# 16-MT7688AN_Power-F.net
KiCad netlist of a schematic drawn in Altium Designer
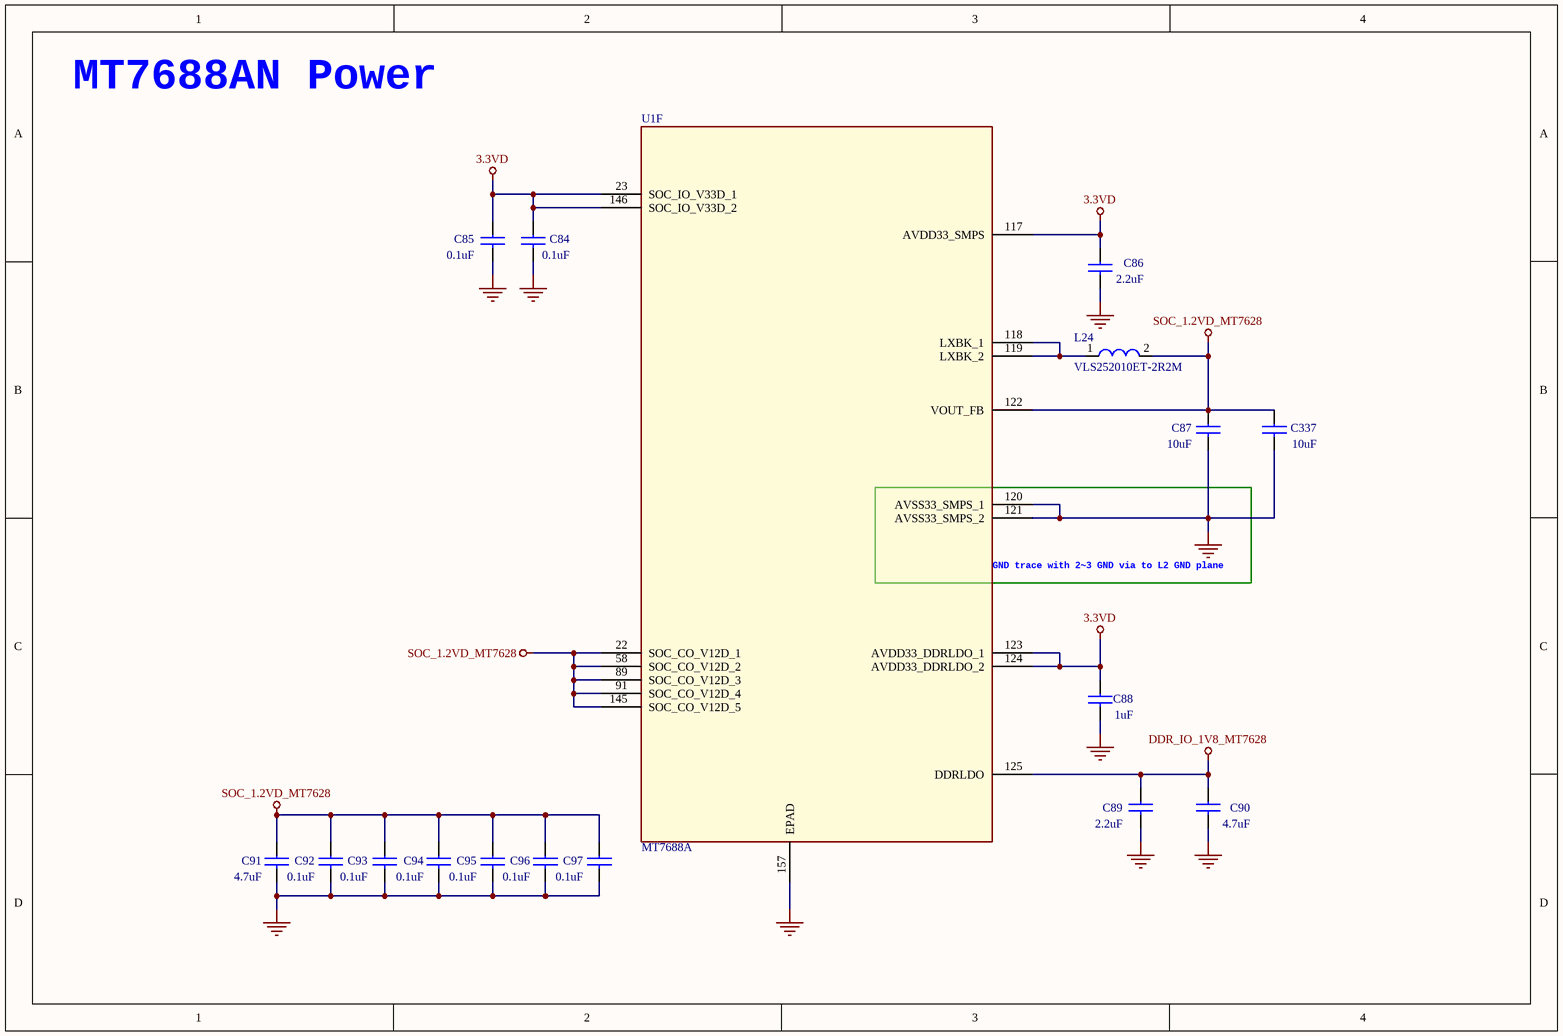
[diagram p0: 16-MT7688AN Power-F.SchDoc]

(export (version "E")
  (design (tool "Eeschema 10.0.6"))
  (components
    (comp (ref "C84")
      (value "0.1uF")
      (footprint "RLC 0201 M35")
      (libsource (lib "LinkIt Air+ (EK-7688AM+)") (part "CAP NP"))
    )
    (comp (ref "C85")
      (value "0.1uF")
      (footprint "RLC 0201 M35")
      (libsource (lib "LinkIt Air+ (EK-7688AM+)") (part "CAP NP"))
    )
    (comp (ref "C86")
      (value "2.2uF")
      (footprint "RLC 0402 M35")
      (libsource (lib "LinkIt Air+ (EK-7688AM+)") (part "CAP NP"))
    )
    (comp (ref "C87")
      (value "10uF")
      (footprint "RLC 0402 M35")
      (libsource (lib "LinkIt Air+ (EK-7688AM+)") (part "CAP NP"))
    )
    (comp (ref "C88")
      (value "1uF")
      (footprint "RLC 0201 M35")
      (libsource (lib "LinkIt Air+ (EK-7688AM+)") (part "CAP NP"))
    )
    (comp (ref "C89")
      (value "2.2uF")
      (footprint "RLC 0402 M35")
      (libsource (lib "LinkIt Air+ (EK-7688AM+)") (part "CAP NP"))
    )
    (comp (ref "C90")
      (value "4.7uF")
      (footprint "RLC 0402 M35")
      (libsource (lib "LinkIt Air+ (EK-7688AM+)") (part "CAP NP"))
    )
    (comp (ref "C91")
      (value "4.7uF")
      (footprint "RLC 0402 M35")
      (libsource (lib "LinkIt Air+ (EK-7688AM+)") (part "CAP NP"))
    )
    (comp (ref "C92")
      (value "0.1uF")
      (footprint "RLC 0201 M35")
      (libsource (lib "LinkIt Air+ (EK-7688AM+)") (part "CAP NP"))
    )
    (comp (ref "C93")
      (value "0.1uF")
      (footprint "RLC 0201 M35")
      (libsource (lib "LinkIt Air+ (EK-7688AM+)") (part "CAP NP"))
    )
    (comp (ref "C94")
      (value "0.1uF")
      (footprint "RLC 0201 M35")
      (libsource (lib "LinkIt Air+ (EK-7688AM+)") (part "CAP NP"))
    )
    (comp (ref "C95")
      (value "0.1uF")
      (footprint "RLC 0201 M35")
      (libsource (lib "LinkIt Air+ (EK-7688AM+)") (part "CAP NP"))
    )
    (comp (ref "C96")
      (value "0.1uF")
      (footprint "RLC 0201 M35")
      (libsource (lib "LinkIt Air+ (EK-7688AM+)") (part "CAP NP"))
    )
    (comp (ref "C97")
      (value "0.1uF")
      (footprint "RLC 0201 M35")
      (libsource (lib "LinkIt Air+ (EK-7688AM+)") (part "CAP NP"))
    )
    (comp (ref "C337")
      (value "10uF")
      (footprint "RLC 0402 M35")
      (libsource (lib "LinkIt Air+ (EK-7688AM+)") (part "CAP NP"))
    )
    (comp (ref "L24")
      (value "VLS252010ET-2R2M")
      (footprint "L/IND/SMD/VLS252010/TDK")
      (description "IND 0805 METAL 2.2uH 0.19R 1.2A T=1.0mm")
      (libsource (lib "LinkIt Air+ (EK-7688AM+)") (part "L/0402"))
    )
    (comp (ref "U1")
      (value "MT7688A")
      (footprint "MT7628AN$2F$DRQFN156$2F$SMD$2F$P0.5$2F$12X12")
      (libsource (lib "LinkIt Air+ (EK-7688AM+)") (part "MT7620N-n_26"))
    )
  )
  (nets
    (net (code "1") (name "3.3VD") (class "Default")
      (node (ref "C84") (pin "1") (pinfunction "1_1") (pintype "passive"))
      (node (ref "C85") (pin "1") (pinfunction "1_1") (pintype "passive"))
      (node (ref "C86") (pin "1") (pinfunction "1_1") (pintype "passive"))
      (node (ref "C88") (pin "1") (pinfunction "1_1") (pintype "passive"))
      (node (ref "U1") (pin "117") (pinfunction "AVDD33_SMPS_117") (pintype "power_in"))
      (node (ref "U1") (pin "123") (pinfunction "AVDD33_DDRLDO_1_123") (pintype "power_in"))
      (node (ref "U1") (pin "124") (pinfunction "AVDD33_DDRLDO_2_124") (pintype "power_in"))
      (node (ref "U1") (pin "146") (pinfunction "SOC_IO_V33D_2_146") (pintype "power_in"))
      (node (ref "U1") (pin "23") (pinfunction "SOC_IO_V33D_1_23") (pintype "power_in"))
    )
    (net (code "2") (name "DDR_IO_1V8_MT7628") (class "Default")
      (node (ref "C89") (pin "1") (pinfunction "1_1") (pintype "passive"))
      (node (ref "C90") (pin "1") (pinfunction "1_1") (pintype "passive"))
      (node (ref "U1") (pin "125") (pinfunction "DDRLDO_125") (pintype "power_in"))
    )
    (net (code "3") (name "GND") (class "Default")
      (node (ref "C337") (pin "2") (pinfunction "2_2") (pintype "passive"))
      (node (ref "C84") (pin "2") (pinfunction "2_2") (pintype "passive"))
      (node (ref "C85") (pin "2") (pinfunction "2_2") (pintype "passive"))
      (node (ref "C86") (pin "2") (pinfunction "2_2") (pintype "passive"))
      (node (ref "C87") (pin "2") (pinfunction "2_2") (pintype "passive"))
      (node (ref "C88") (pin "2") (pinfunction "2_2") (pintype "passive"))
      (node (ref "C89") (pin "2") (pinfunction "2_2") (pintype "passive"))
      (node (ref "C90") (pin "2") (pinfunction "2_2") (pintype "passive"))
      (node (ref "C91") (pin "2") (pinfunction "2_2") (pintype "passive"))
      (node (ref "C92") (pin "2") (pinfunction "2_2") (pintype "passive"))
      (node (ref "C93") (pin "2") (pinfunction "2_2") (pintype "passive"))
      (node (ref "C94") (pin "2") (pinfunction "2_2") (pintype "passive"))
      (node (ref "C95") (pin "2") (pinfunction "2_2") (pintype "passive"))
      (node (ref "C96") (pin "2") (pinfunction "2_2") (pintype "passive"))
      (node (ref "C97") (pin "2") (pinfunction "2_2") (pintype "passive"))
      (node (ref "U1") (pin "120") (pinfunction "AVSS33_SMPS_1_120") (pintype "power_in"))
      (node (ref "U1") (pin "121") (pinfunction "AVSS33_SMPS_2_121") (pintype "power_in"))
      (node (ref "U1") (pin "157") (pinfunction "EPAD_157") (pintype "power_in"))
    )
    (net (code "4") (name "Net-(U1F-LXBK_1)") (class "Default")
      (node (ref "L24") (pin "1") (pinfunction "1_1") (pintype "passive"))
      (node (ref "U1") (pin "118") (pinfunction "LXBK_1_118") (pintype "passive"))
      (node (ref "U1") (pin "119") (pinfunction "LXBK_2_119") (pintype "passive"))
    )
    (net (code "5") (name "SOC_1.2VD_MT7628") (class "Default")
      (node (ref "C337") (pin "1") (pinfunction "1_1") (pintype "passive"))
      (node (ref "C87") (pin "1") (pinfunction "1_1") (pintype "passive"))
      (node (ref "C91") (pin "1") (pinfunction "1_1") (pintype "passive"))
      (node (ref "C92") (pin "1") (pinfunction "1_1") (pintype "passive"))
      (node (ref "C93") (pin "1") (pinfunction "1_1") (pintype "passive"))
      (node (ref "C94") (pin "1") (pinfunction "1_1") (pintype "passive"))
      (node (ref "C95") (pin "1") (pinfunction "1_1") (pintype "passive"))
      (node (ref "C96") (pin "1") (pinfunction "1_1") (pintype "passive"))
      (node (ref "C97") (pin "1") (pinfunction "1_1") (pintype "passive"))
      (node (ref "L24") (pin "2") (pinfunction "2_2") (pintype "passive"))
      (node (ref "U1") (pin "122") (pinfunction "VOUT_FB_122") (pintype "power_in"))
      (node (ref "U1") (pin "145") (pinfunction "SOC_CO_V12D_5_145") (pintype "power_in"))
      (node (ref "U1") (pin "22") (pinfunction "SOC_CO_V12D_1_22") (pintype "power_in"))
      (node (ref "U1") (pin "58") (pinfunction "SOC_CO_V12D_2_58") (pintype "power_in"))
      (node (ref "U1") (pin "89") (pinfunction "SOC_CO_V12D_3_89") (pintype "power_in"))
      (node (ref "U1") (pin "91") (pinfunction "SOC_CO_V12D_4_91") (pintype "power_in"))
    )
  )
)
